# LED-PCB_DIG1.net
KiCad netlist of a schematic drawn in Altium Designer
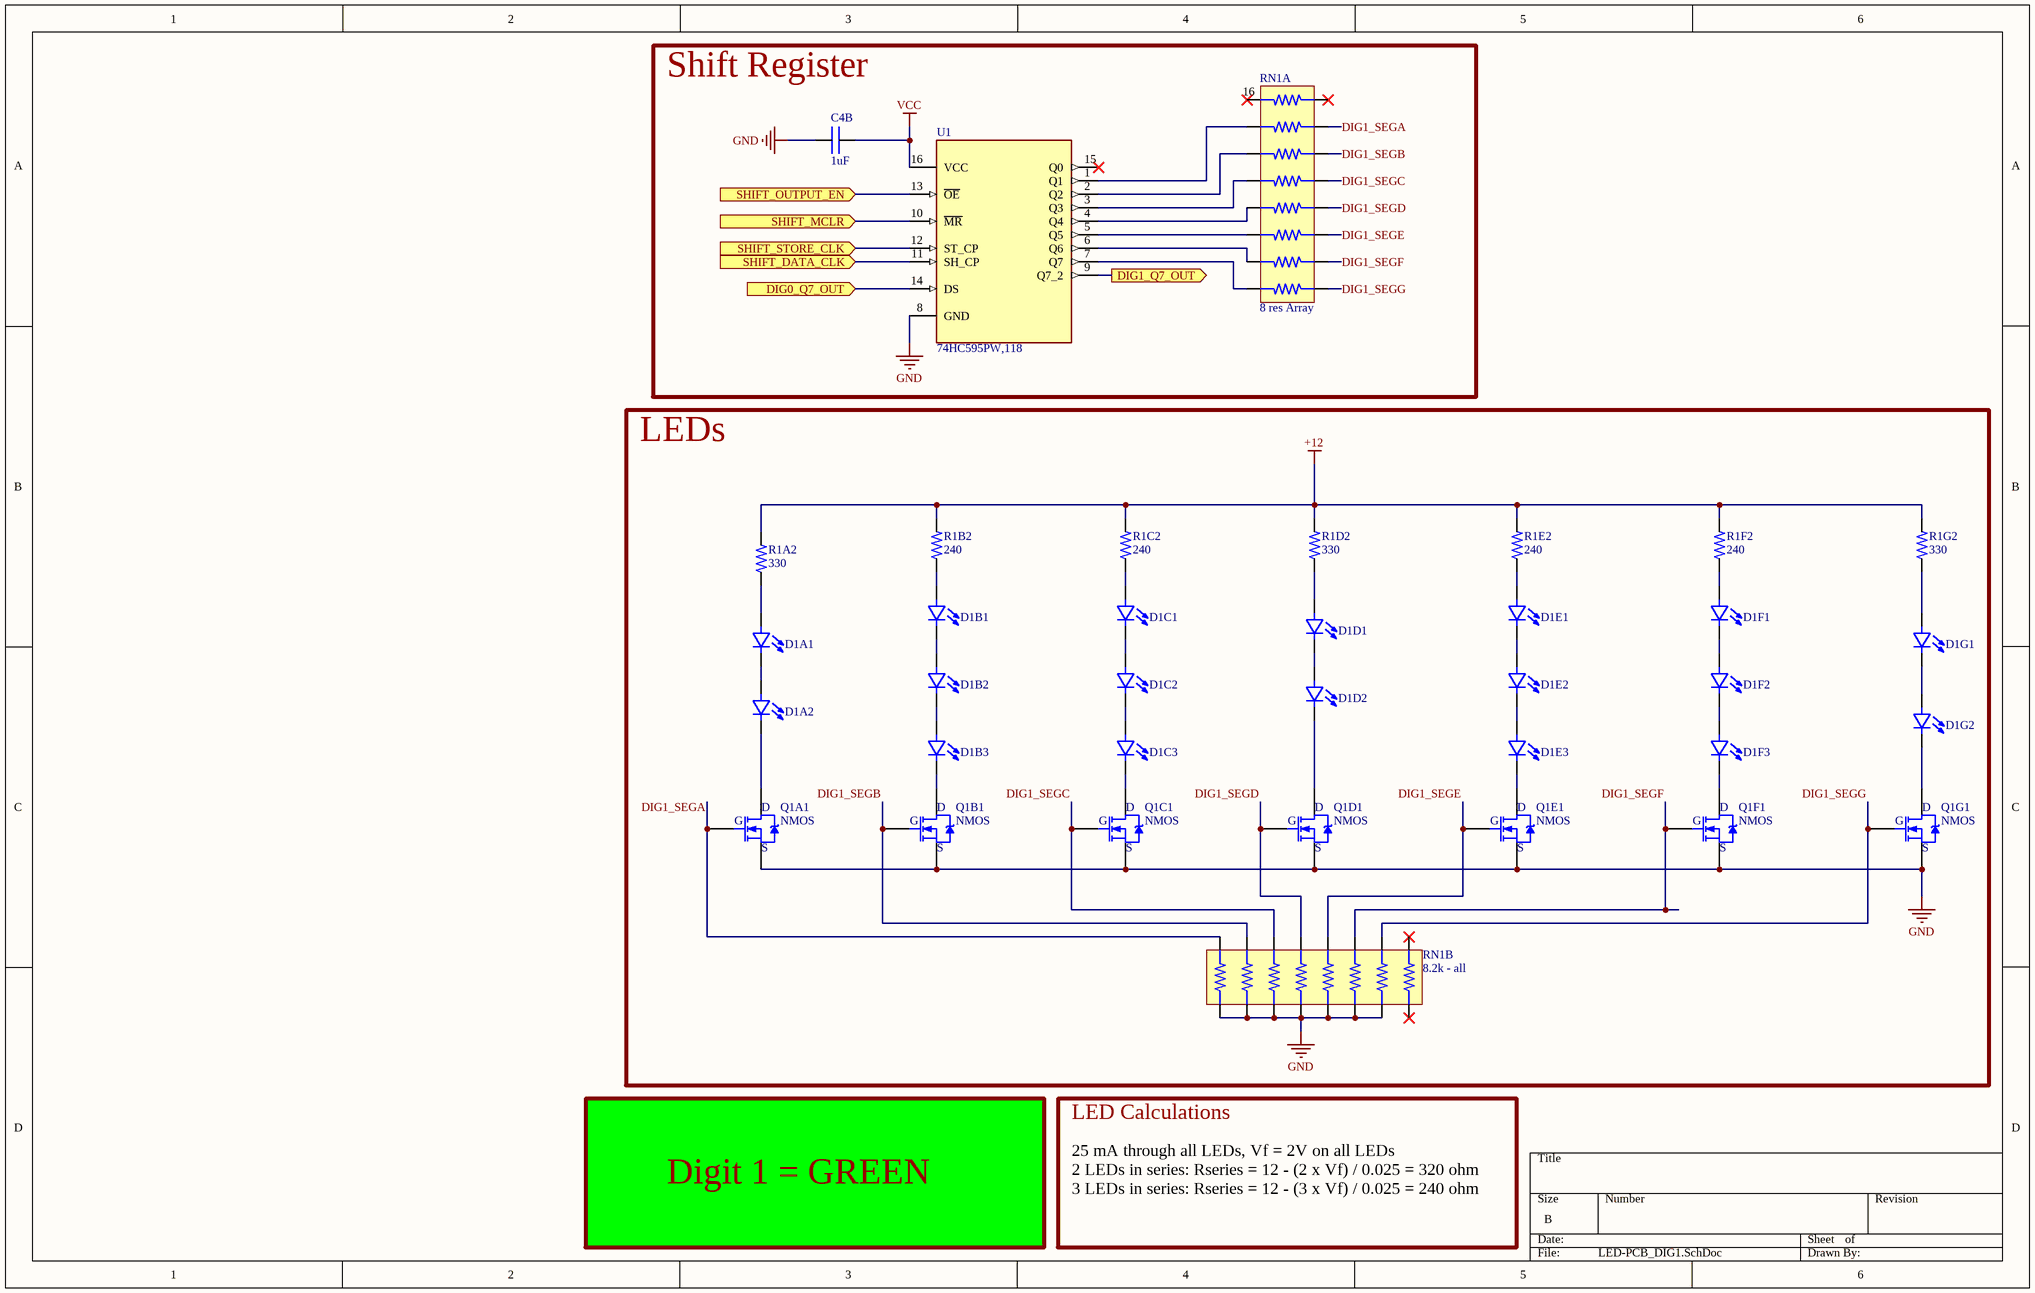
[diagram p0: LED-PCB_DIG1.SchDoc]

(export (version "E")
  (design (tool "Eeschema 10.0.6"))
  (components
    (comp (ref "C4B")
      (value "1uF")
      (footprint "sinking-clock:0402 CAP")
      (description "Capaicitor")
      (fields (field (name "PART NUMBER") "CL05A105KP5NNNC") (field (name "Comment") "CAP"))
      (libsource (lib "sinking-clock") (part "CAP"))
    )
    (comp (ref "D1A1")
      (value "LED - single")
      (footprint "sinking-clock:LED - 0603")
      (fields (field (name "PART NUMBER") "150060RS75000"))
      (libsource (lib "sinking-clock") (part "LED - single"))
    )
    (comp (ref "D1A2")
      (value "LED - single")
      (footprint "sinking-clock:LED - 0603")
      (fields (field (name "PART NUMBER") "150060RS75000"))
      (libsource (lib "sinking-clock") (part "LED - single"))
    )
    (comp (ref "D1B1")
      (value "LED - single")
      (footprint "sinking-clock:LED - 0603")
      (fields (field (name "PART NUMBER") "150060RS75000"))
      (libsource (lib "sinking-clock") (part "LED - single"))
    )
    (comp (ref "D1B2")
      (value "LED - single")
      (footprint "sinking-clock:LED - 0603")
      (fields (field (name "PART NUMBER") "150060RS75000"))
      (libsource (lib "sinking-clock") (part "LED - single"))
    )
    (comp (ref "D1B3")
      (value "LED - single")
      (footprint "sinking-clock:LED - 0603")
      (fields (field (name "PART NUMBER") "150060RS75000"))
      (libsource (lib "sinking-clock") (part "LED - single"))
    )
    (comp (ref "D1C1")
      (value "LED - single")
      (footprint "sinking-clock:LED - 0603")
      (fields (field (name "PART NUMBER") "150060RS75000"))
      (libsource (lib "sinking-clock") (part "LED - single"))
    )
    (comp (ref "D1C2")
      (value "LED - single")
      (footprint "sinking-clock:LED - 0603")
      (fields (field (name "PART NUMBER") "150060RS75000"))
      (libsource (lib "sinking-clock") (part "LED - single"))
    )
    (comp (ref "D1C3")
      (value "LED - single")
      (footprint "sinking-clock:LED - 0603")
      (fields (field (name "PART NUMBER") "150060RS75000"))
      (libsource (lib "sinking-clock") (part "LED - single"))
    )
    (comp (ref "D1D1")
      (value "LED - single")
      (footprint "sinking-clock:LED - 0603")
      (fields (field (name "PART NUMBER") "150060RS75000"))
      (libsource (lib "sinking-clock") (part "LED - single"))
    )
    (comp (ref "D1D2")
      (value "LED - single")
      (footprint "sinking-clock:LED - 0603")
      (fields (field (name "PART NUMBER") "150060RS75000"))
      (libsource (lib "sinking-clock") (part "LED - single"))
    )
    (comp (ref "D1E1")
      (value "LED - single")
      (footprint "sinking-clock:LED - 0603")
      (fields (field (name "PART NUMBER") "150060RS75000"))
      (libsource (lib "sinking-clock") (part "LED - single"))
    )
    (comp (ref "D1E2")
      (value "LED - single")
      (footprint "sinking-clock:LED - 0603")
      (fields (field (name "PART NUMBER") "150060RS75000"))
      (libsource (lib "sinking-clock") (part "LED - single"))
    )
    (comp (ref "D1E3")
      (value "LED - single")
      (footprint "sinking-clock:LED - 0603")
      (fields (field (name "PART NUMBER") "150060RS75000"))
      (libsource (lib "sinking-clock") (part "LED - single"))
    )
    (comp (ref "D1F1")
      (value "LED - single")
      (footprint "sinking-clock:LED - 0603")
      (fields (field (name "PART NUMBER") "150060RS75000"))
      (libsource (lib "sinking-clock") (part "LED - single"))
    )
    (comp (ref "D1F2")
      (value "LED - single")
      (footprint "sinking-clock:LED - 0603")
      (fields (field (name "PART NUMBER") "150060RS75000"))
      (libsource (lib "sinking-clock") (part "LED - single"))
    )
    (comp (ref "D1F3")
      (value "LED - single")
      (footprint "sinking-clock:LED - 0603")
      (fields (field (name "PART NUMBER") "150060RS75000"))
      (libsource (lib "sinking-clock") (part "LED - single"))
    )
    (comp (ref "D1G1")
      (value "LED - single")
      (footprint "sinking-clock:LED - 0603")
      (fields (field (name "PART NUMBER") "150060RS75000"))
      (libsource (lib "sinking-clock") (part "LED - single"))
    )
    (comp (ref "D1G2")
      (value "LED - single")
      (footprint "sinking-clock:LED - 0603")
      (fields (field (name "PART NUMBER") "150060RS75000"))
      (libsource (lib "sinking-clock") (part "LED - single"))
    )
    (comp (ref "Q1A1")
      (value "NMOS")
      (footprint "sinking-clock:SOT-23")
      (description "N-Channel MOSFET")
      (fields (field (name "PART NUMBER") "DMN63D8L"))
      (libsource (lib "sinking-clock") (part "NMOS"))
    )
    (comp (ref "Q1B1")
      (value "NMOS")
      (footprint "sinking-clock:SOT-23")
      (description "N-Channel MOSFET")
      (fields (field (name "PART NUMBER") "DMN63D8L"))
      (libsource (lib "sinking-clock") (part "NMOS"))
    )
    (comp (ref "Q1C1")
      (value "NMOS")
      (footprint "sinking-clock:SOT-23")
      (description "N-Channel MOSFET")
      (fields (field (name "PART NUMBER") "DMN63D8L"))
      (libsource (lib "sinking-clock") (part "NMOS"))
    )
    (comp (ref "Q1D1")
      (value "NMOS")
      (footprint "sinking-clock:SOT-23")
      (description "N-Channel MOSFET")
      (fields (field (name "PART NUMBER") "DMN63D8L"))
      (libsource (lib "sinking-clock") (part "NMOS"))
    )
    (comp (ref "Q1E1")
      (value "NMOS")
      (footprint "sinking-clock:SOT-23")
      (description "N-Channel MOSFET")
      (fields (field (name "PART NUMBER") "DMN63D8L"))
      (libsource (lib "sinking-clock") (part "NMOS"))
    )
    (comp (ref "Q1F1")
      (value "NMOS")
      (footprint "sinking-clock:SOT-23")
      (description "N-Channel MOSFET")
      (fields (field (name "PART NUMBER") "DMN63D8L"))
      (libsource (lib "sinking-clock") (part "NMOS"))
    )
    (comp (ref "Q1G1")
      (value "NMOS")
      (footprint "sinking-clock:SOT-23")
      (description "N-Channel MOSFET")
      (fields (field (name "PART NUMBER") "DMN63D8L"))
      (libsource (lib "sinking-clock") (part "NMOS"))
    )
    (comp (ref "R1A2")
      (value "330")
      (footprint "sinking-clock:0402 RES")
      (description "Resistor")
      (fields (field (name "PART NUMBER") "RC0402JR-13330RL") (field (name "Comment") "RES"))
      (libsource (lib "sinking-clock") (part "RES"))
    )
    (comp (ref "R1B2")
      (value "240")
      (footprint "sinking-clock:0402 RES")
      (description "Resistor")
      (fields (field (name "PART NUMBER") "RC0402FR-07240RL") (field (name "Comment") "RES"))
      (libsource (lib "sinking-clock") (part "RES"))
    )
    (comp (ref "R1C2")
      (value "240")
      (footprint "sinking-clock:0402 RES")
      (description "Resistor")
      (fields (field (name "PART NUMBER") "RC0402FR-07240RL") (field (name "Comment") "RES"))
      (libsource (lib "sinking-clock") (part "RES"))
    )
    (comp (ref "R1D2")
      (value "330")
      (footprint "sinking-clock:0402 RES")
      (description "Resistor")
      (fields (field (name "PART NUMBER") "RC0402JR-13330RL") (field (name "Comment") "RES"))
      (libsource (lib "sinking-clock") (part "RES"))
    )
    (comp (ref "R1E2")
      (value "240")
      (footprint "sinking-clock:0402 RES")
      (description "Resistor")
      (fields (field (name "PART NUMBER") "RC0402FR-07240RL") (field (name "Comment") "RES"))
      (libsource (lib "sinking-clock") (part "RES"))
    )
    (comp (ref "R1F2")
      (value "240")
      (footprint "sinking-clock:0402 RES")
      (description "Resistor")
      (fields (field (name "PART NUMBER") "RC0402FR-07240RL") (field (name "Comment") "RES"))
      (libsource (lib "sinking-clock") (part "RES"))
    )
    (comp (ref "R1G2")
      (value "330")
      (footprint "sinking-clock:0402 RES")
      (description "Resistor")
      (fields (field (name "PART NUMBER") "RC0402JR-13330RL") (field (name "Comment") "RES"))
      (libsource (lib "sinking-clock") (part "RES"))
    )
    (comp (ref "RN1A")
      (value "8 res Array")
      (footprint "sinking-clock:EXB2HV331JV")
      (libsource (lib "sinking-clock") (part "8 res Array"))
    )
    (comp (ref "RN1B")
      (value "8.2k - all")
      (footprint "sinking-clock:MNR18ERAPJ822")
      (fields (field (name "PART NUMBER") "MNR18ERAPJ822"))
      (libsource (lib "sinking-clock") (part "MNR18ERAPJ822"))
    )
    (comp (ref "U1")
      (value "74HC595PW,118")
      (footprint "sinking-clock:16-TSSOP")
      (description "Shift Shift Register 1 Element 8 Bit 16-TSSOP")
      (libsource (lib "sinking-clock") (part "74HC595PW,118"))
    )
  )
  (nets
    (net (code "1") (name "+12") (class "Default")
      (node (ref "R1A2") (pin "2") (pinfunction "2_2") (pintype "passive"))
      (node (ref "R1B2") (pin "2") (pinfunction "2_2") (pintype "passive"))
      (node (ref "R1C2") (pin "2") (pinfunction "2_2") (pintype "passive"))
      (node (ref "R1D2") (pin "2") (pinfunction "2_2") (pintype "passive"))
      (node (ref "R1E2") (pin "2") (pinfunction "2_2") (pintype "passive"))
      (node (ref "R1F2") (pin "2") (pinfunction "2_2") (pintype "passive"))
      (node (ref "R1G2") (pin "2") (pinfunction "2_2") (pintype "passive"))
    )
    (net (code "2") (name "/DIG0_Q7_OUT") (class "Default")
      (node (ref "U1") (pin "14") (pinfunction "DS_14") (pintype "input"))
    )
    (net (code "3") (name "/DIG1_Q7_OUT") (class "Default")
      (node (ref "U1") (pin "9") (pinfunction "Q7_2_9") (pintype "output"))
    )
    (net (code "4") (name "/DIG1_SEGA") (class "Default")
      (node (ref "Q1A1") (pin "1") (pinfunction "G_1") (pintype "passive"))
      (node (ref "RN1A") (pin "2") (pinfunction "2_2") (pintype "passive"))
      (node (ref "RN1B") (pin "16") (pinfunction "16_16") (pintype "passive"))
    )
    (net (code "5") (name "/DIG1_SEGB") (class "Default")
      (node (ref "Q1B1") (pin "1") (pinfunction "G_1") (pintype "passive"))
      (node (ref "RN1A") (pin "3") (pinfunction "3_3") (pintype "passive"))
      (node (ref "RN1B") (pin "15") (pinfunction "15_15") (pintype "passive"))
    )
    (net (code "6") (name "/DIG1_SEGC") (class "Default")
      (node (ref "Q1C1") (pin "1") (pinfunction "G_1") (pintype "passive"))
      (node (ref "RN1A") (pin "4") (pinfunction "4_4") (pintype "passive"))
      (node (ref "RN1B") (pin "14") (pinfunction "14_14") (pintype "passive"))
    )
    (net (code "7") (name "/DIG1_SEGD") (class "Default")
      (node (ref "Q1D1") (pin "1") (pinfunction "G_1") (pintype "passive"))
      (node (ref "RN1A") (pin "5") (pinfunction "5_5") (pintype "passive"))
      (node (ref "RN1B") (pin "13") (pinfunction "13_13") (pintype "passive"))
    )
    (net (code "8") (name "/DIG1_SEGE") (class "Default")
      (node (ref "Q1E1") (pin "1") (pinfunction "G_1") (pintype "passive"))
      (node (ref "RN1A") (pin "6") (pinfunction "6_6") (pintype "passive"))
      (node (ref "RN1B") (pin "12") (pinfunction "12_12") (pintype "passive"))
    )
    (net (code "9") (name "/DIG1_SEGF") (class "Default")
      (node (ref "Q1F1") (pin "1") (pinfunction "G_1") (pintype "passive"))
      (node (ref "RN1A") (pin "7") (pinfunction "7_7") (pintype "passive"))
      (node (ref "RN1B") (pin "11") (pinfunction "11_11") (pintype "passive"))
    )
    (net (code "10") (name "/DIG1_SEGG") (class "Default")
      (node (ref "Q1G1") (pin "1") (pinfunction "G_1") (pintype "passive"))
      (node (ref "RN1A") (pin "8") (pinfunction "8_8") (pintype "passive"))
      (node (ref "RN1B") (pin "10") (pinfunction "10_10") (pintype "passive"))
    )
    (net (code "11") (name "/SHIFT_DATA_CLK") (class "Default")
      (node (ref "U1") (pin "11") (pinfunction "SH_CP_11") (pintype "input"))
    )
    (net (code "12") (name "/SHIFT_MCLR") (class "Default")
      (node (ref "U1") (pin "10") (pinfunction "~{MR}_10") (pintype "input"))
    )
    (net (code "13") (name "/SHIFT_OUTPUT_EN") (class "Default")
      (node (ref "U1") (pin "13") (pinfunction "~{OE}_13") (pintype "input"))
    )
    (net (code "14") (name "/SHIFT_STORE_CLK") (class "Default")
      (node (ref "U1") (pin "12") (pinfunction "ST_CP_12") (pintype "input"))
    )
    (net (code "15") (name "GND") (class "Default")
      (node (ref "C4B") (pin "1") (pinfunction "1_1") (pintype "passive"))
      (node (ref "Q1A1") (pin "2") (pinfunction "S_2") (pintype "passive"))
      (node (ref "Q1B1") (pin "2") (pinfunction "S_2") (pintype "passive"))
      (node (ref "Q1C1") (pin "2") (pinfunction "S_2") (pintype "passive"))
      (node (ref "Q1D1") (pin "2") (pinfunction "S_2") (pintype "passive"))
      (node (ref "Q1E1") (pin "2") (pinfunction "S_2") (pintype "passive"))
      (node (ref "Q1F1") (pin "2") (pinfunction "S_2") (pintype "passive"))
      (node (ref "Q1G1") (pin "2") (pinfunction "S_2") (pintype "passive"))
      (node (ref "RN1B") (pin "1") (pinfunction "1_1") (pintype "passive"))
      (node (ref "RN1B") (pin "2") (pinfunction "2_2") (pintype "passive"))
      (node (ref "RN1B") (pin "3") (pinfunction "3_3") (pintype "passive"))
      (node (ref "RN1B") (pin "4") (pinfunction "4_4") (pintype "passive"))
      (node (ref "RN1B") (pin "5") (pinfunction "5_5") (pintype "passive"))
      (node (ref "RN1B") (pin "6") (pinfunction "6_6") (pintype "passive"))
      (node (ref "RN1B") (pin "7") (pinfunction "7_7") (pintype "passive"))
      (node (ref "U1") (pin "8") (pinfunction "GND_8") (pintype "passive"))
    )
    (net (code "16") (name "Net-(D1A1-A)") (class "Default")
      (node (ref "D1A1") (pin "1") (pinfunction "A_1") (pintype "passive"))
      (node (ref "R1A2") (pin "1") (pinfunction "1_1") (pintype "passive"))
    )
    (net (code "17") (name "Net-(D1A1-C)") (class "Default")
      (node (ref "D1A1") (pin "2") (pinfunction "C_2") (pintype "passive"))
      (node (ref "D1A2") (pin "1") (pinfunction "A_1") (pintype "passive"))
    )
    (net (code "18") (name "Net-(D1A2-C)") (class "Default")
      (node (ref "D1A2") (pin "2") (pinfunction "C_2") (pintype "passive"))
      (node (ref "Q1A1") (pin "3") (pinfunction "D_3") (pintype "passive"))
    )
    (net (code "19") (name "Net-(D1B1-A)") (class "Default")
      (node (ref "D1B1") (pin "1") (pinfunction "A_1") (pintype "passive"))
      (node (ref "R1B2") (pin "1") (pinfunction "1_1") (pintype "passive"))
    )
    (net (code "20") (name "Net-(D1B1-C)") (class "Default")
      (node (ref "D1B1") (pin "2") (pinfunction "C_2") (pintype "passive"))
      (node (ref "D1B2") (pin "1") (pinfunction "A_1") (pintype "passive"))
    )
    (net (code "21") (name "Net-(D1B2-C)") (class "Default")
      (node (ref "D1B2") (pin "2") (pinfunction "C_2") (pintype "passive"))
      (node (ref "D1B3") (pin "1") (pinfunction "A_1") (pintype "passive"))
    )
    (net (code "22") (name "Net-(D1B3-C)") (class "Default")
      (node (ref "D1B3") (pin "2") (pinfunction "C_2") (pintype "passive"))
      (node (ref "Q1B1") (pin "3") (pinfunction "D_3") (pintype "passive"))
    )
    (net (code "23") (name "Net-(D1C1-A)") (class "Default")
      (node (ref "D1C1") (pin "1") (pinfunction "A_1") (pintype "passive"))
      (node (ref "R1C2") (pin "1") (pinfunction "1_1") (pintype "passive"))
    )
    (net (code "24") (name "Net-(D1C1-C)") (class "Default")
      (node (ref "D1C1") (pin "2") (pinfunction "C_2") (pintype "passive"))
      (node (ref "D1C2") (pin "1") (pinfunction "A_1") (pintype "passive"))
    )
    (net (code "25") (name "Net-(D1C2-C)") (class "Default")
      (node (ref "D1C2") (pin "2") (pinfunction "C_2") (pintype "passive"))
      (node (ref "D1C3") (pin "1") (pinfunction "A_1") (pintype "passive"))
    )
    (net (code "26") (name "Net-(D1C3-C)") (class "Default")
      (node (ref "D1C3") (pin "2") (pinfunction "C_2") (pintype "passive"))
      (node (ref "Q1C1") (pin "3") (pinfunction "D_3") (pintype "passive"))
    )
    (net (code "27") (name "Net-(D1D1-A)") (class "Default")
      (node (ref "D1D1") (pin "1") (pinfunction "A_1") (pintype "passive"))
      (node (ref "R1D2") (pin "1") (pinfunction "1_1") (pintype "passive"))
    )
    (net (code "28") (name "Net-(D1D1-C)") (class "Default")
      (node (ref "D1D1") (pin "2") (pinfunction "C_2") (pintype "passive"))
      (node (ref "D1D2") (pin "1") (pinfunction "A_1") (pintype "passive"))
    )
    (net (code "29") (name "Net-(D1D2-C)") (class "Default")
      (node (ref "D1D2") (pin "2") (pinfunction "C_2") (pintype "passive"))
      (node (ref "Q1D1") (pin "3") (pinfunction "D_3") (pintype "passive"))
    )
    (net (code "30") (name "Net-(D1E1-A)") (class "Default")
      (node (ref "D1E1") (pin "1") (pinfunction "A_1") (pintype "passive"))
      (node (ref "R1E2") (pin "1") (pinfunction "1_1") (pintype "passive"))
    )
    (net (code "31") (name "Net-(D1E1-C)") (class "Default")
      (node (ref "D1E1") (pin "2") (pinfunction "C_2") (pintype "passive"))
      (node (ref "D1E2") (pin "1") (pinfunction "A_1") (pintype "passive"))
    )
    (net (code "32") (name "Net-(D1E2-C)") (class "Default")
      (node (ref "D1E2") (pin "2") (pinfunction "C_2") (pintype "passive"))
      (node (ref "D1E3") (pin "1") (pinfunction "A_1") (pintype "passive"))
    )
    (net (code "33") (name "Net-(D1E3-C)") (class "Default")
      (node (ref "D1E3") (pin "2") (pinfunction "C_2") (pintype "passive"))
      (node (ref "Q1E1") (pin "3") (pinfunction "D_3") (pintype "passive"))
    )
    (net (code "34") (name "Net-(D1F1-A)") (class "Default")
      (node (ref "D1F1") (pin "1") (pinfunction "A_1") (pintype "passive"))
      (node (ref "R1F2") (pin "1") (pinfunction "1_1") (pintype "passive"))
    )
    (net (code "35") (name "Net-(D1F1-C)") (class "Default")
      (node (ref "D1F1") (pin "2") (pinfunction "C_2") (pintype "passive"))
      (node (ref "D1F2") (pin "1") (pinfunction "A_1") (pintype "passive"))
    )
    (net (code "36") (name "Net-(D1F2-C)") (class "Default")
      (node (ref "D1F2") (pin "2") (pinfunction "C_2") (pintype "passive"))
      (node (ref "D1F3") (pin "1") (pinfunction "A_1") (pintype "passive"))
    )
    (net (code "37") (name "Net-(D1F3-C)") (class "Default")
      (node (ref "D1F3") (pin "2") (pinfunction "C_2") (pintype "passive"))
      (node (ref "Q1F1") (pin "3") (pinfunction "D_3") (pintype "passive"))
    )
    (net (code "38") (name "Net-(D1G1-A)") (class "Default")
      (node (ref "D1G1") (pin "1") (pinfunction "A_1") (pintype "passive"))
      (node (ref "R1G2") (pin "1") (pinfunction "1_1") (pintype "passive"))
    )
    (net (code "39") (name "Net-(D1G1-C)") (class "Default")
      (node (ref "D1G1") (pin "2") (pinfunction "C_2") (pintype "passive"))
      (node (ref "D1G2") (pin "1") (pinfunction "A_1") (pintype "passive"))
    )
    (net (code "40") (name "Net-(D1G2-C)") (class "Default")
      (node (ref "D1G2") (pin "2") (pinfunction "C_2") (pintype "passive"))
      (node (ref "Q1G1") (pin "3") (pinfunction "D_3") (pintype "passive"))
    )
    (net (code "41") (name "Net-(U1-Q1)") (class "Default")
      (node (ref "RN1A") (pin "15") (pinfunction "15_15") (pintype "passive"))
      (node (ref "U1") (pin "1") (pinfunction "Q1_1") (pintype "output"))
    )
    (net (code "42") (name "Net-(U1-Q2)") (class "Default")
      (node (ref "RN1A") (pin "14") (pinfunction "14_14") (pintype "passive"))
      (node (ref "U1") (pin "2") (pinfunction "Q2_2") (pintype "output"))
    )
    (net (code "43") (name "Net-(U1-Q3)") (class "Default")
      (node (ref "RN1A") (pin "13") (pinfunction "13_13") (pintype "passive"))
      (node (ref "U1") (pin "3") (pinfunction "Q3_3") (pintype "output"))
    )
    (net (code "44") (name "Net-(U1-Q4)") (class "Default")
      (node (ref "RN1A") (pin "12") (pinfunction "12_12") (pintype "passive"))
      (node (ref "U1") (pin "4") (pinfunction "Q4_4") (pintype "output"))
    )
    (net (code "45") (name "Net-(U1-Q5)") (class "Default")
      (node (ref "RN1A") (pin "11") (pinfunction "11_11") (pintype "passive"))
      (node (ref "U1") (pin "5") (pinfunction "Q5_5") (pintype "output"))
    )
    (net (code "46") (name "Net-(U1-Q6)") (class "Default")
      (node (ref "RN1A") (pin "10") (pinfunction "10_10") (pintype "passive"))
      (node (ref "U1") (pin "6") (pinfunction "Q6_6") (pintype "output"))
    )
    (net (code "47") (name "Net-(U1-Q7)") (class "Default")
      (node (ref "RN1A") (pin "9") (pinfunction "9_9") (pintype "passive"))
      (node (ref "U1") (pin "7") (pinfunction "Q7_7") (pintype "output"))
    )
    (net (code "48") (name "VCC") (class "Default")
      (node (ref "C4B") (pin "2") (pinfunction "2_2") (pintype "passive"))
      (node (ref "U1") (pin "16") (pinfunction "VCC_16") (pintype "power_in"))
    )
    (net (code "49") (name "unconnected-(RN1A-Pad1)") (class "Default")
      (node (ref "RN1A") (pin "1") (pinfunction "1_1") (pintype "passive+no_connect"))
    )
    (net (code "50") (name "unconnected-(RN1A-Pad16)") (class "Default")
      (node (ref "RN1A") (pin "16") (pinfunction "16_16") (pintype "passive+no_connect"))
    )
    (net (code "51") (name "unconnected-(RN1B-Pad8)") (class "Default")
      (node (ref "RN1B") (pin "8") (pinfunction "8_8") (pintype "passive+no_connect"))
    )
    (net (code "52") (name "unconnected-(RN1B-Pad9)") (class "Default")
      (node (ref "RN1B") (pin "9") (pinfunction "9_9") (pintype "passive+no_connect"))
    )
    (net (code "53") (name "unconnected-(U1-Q0-Pad15)") (class "Default")
      (node (ref "U1") (pin "15") (pinfunction "Q0_15") (pintype "output+no_connect"))
    )
  )
)
